# 24Vto5Vat1A-R1.net
KiCad netlist of a schematic drawn in Altium Designer
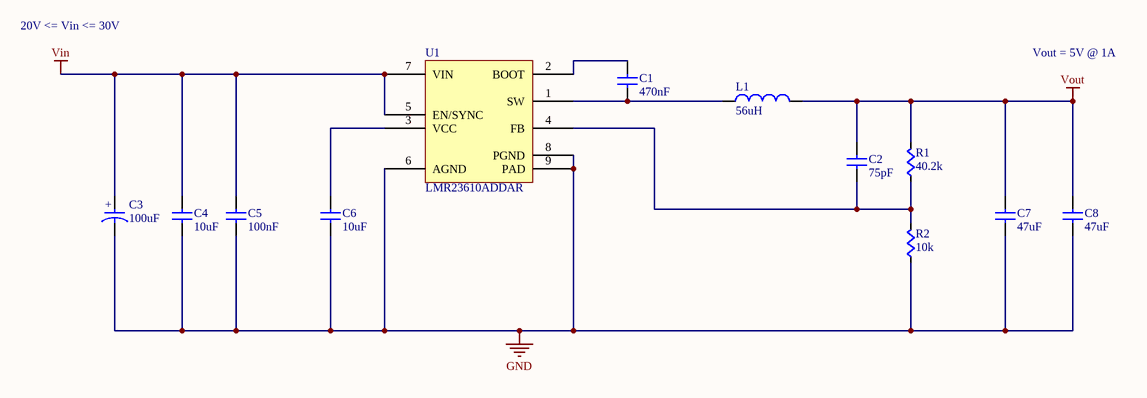
[diagram p0: 24Vto5Vat1A-R1.SchDoc]

(export (version "E")
  (design (tool "Eeschema 10.0.6"))
  (components
    (comp (ref "C1")
      (value "470nF")
      (footprint "CAPC0603")
      (fields (field (name "Comment") "Cap"))
      (libsource (lib "Passives") (part "Cap"))
    )
    (comp (ref "C2")
      (value "75pF")
      (footprint "CAPC0603")
      (fields (field (name "Comment") "Cap"))
      (libsource (lib "Passives") (part "Cap"))
    )
    (comp (ref "C3")
      (value "100uF")
      (footprint "EEHZA1H101P")
      (description "CAP ALUM POLY HYB 100UF 50V SMD")
      (fields (field (name "VOLTAGE") "50V") (field (name "TOLERANCE") "20%"))
      (libsource (lib "SubjuGator8") (part "EEHZA1H101P"))
    )
    (comp (ref "C4")
      (value "10uF")
      (footprint "CAP1210")
      (fields (field (name "Comment") "Cap"))
      (libsource (lib "Passives") (part "Cap"))
    )
    (comp (ref "C5")
      (value "100nF")
      (footprint "CAPC0603")
      (fields (field (name "Comment") "Cap"))
      (libsource (lib "Passives") (part "Cap"))
    )
    (comp (ref "C6")
      (value "10uF")
      (footprint "CAPC0603")
      (fields (field (name "Comment") "Cap"))
      (libsource (lib "Passives") (part "Cap"))
    )
    (comp (ref "C7")
      (value "47uF")
      (footprint "CAP1210")
      (fields (field (name "Comment") "Cap"))
      (libsource (lib "SubjuGator8") (part "Cap"))
    )
    (comp (ref "C8")
      (value "47uF")
      (footprint "CAP1210")
      (fields (field (name "Comment") "Cap"))
      (libsource (lib "SubjuGator8") (part "Cap"))
    )
    (comp (ref "L1")
      (value "56uH")
      (footprint "MSS1048-563MLB")
      (description "FIXED IND 56UH 1.7A 126 MOHM")
      (fields (field (name "Comment") "MSS1048-563MLB"))
      (libsource (lib "SubjuGator8") (part "MSS1048-563MLB"))
    )
    (comp (ref "R1")
      (value "40.2k")
      (footprint "RES0603")
      (fields (field (name "Comment") "Res"))
      (libsource (lib "SubjuGator8") (part "Res"))
    )
    (comp (ref "R2")
      (value "10k")
      (footprint "RES0603")
      (fields (field (name "Comment") "Res"))
      (libsource (lib "SubjuGator8") (part "Res"))
    )
    (comp (ref "U1")
      (value "LMR23610ADDAR")
      (footprint "LMR23610ADDAR")
      (description "IC REG BUCK ADJ 1A SYNC 8SOPWRPD")
      (libsource (lib "SubjuGator8") (part "LMR23610ADDAR"))
    )
  )
  (nets
    (net (code "1") (name "GND") (class "Default")
      (node (ref "C3") (pin "2") (pinfunction "2_2") (pintype "passive"))
      (node (ref "C4") (pin "2") (pinfunction "B_2") (pintype "passive"))
      (node (ref "C5") (pin "2") (pinfunction "B_2") (pintype "passive"))
      (node (ref "C6") (pin "2") (pinfunction "B_2") (pintype "passive"))
      (node (ref "C7") (pin "2") (pinfunction "B_2") (pintype "passive"))
      (node (ref "C8") (pin "2") (pinfunction "B_2") (pintype "passive"))
      (node (ref "R2") (pin "2") (pinfunction "B_2") (pintype "passive"))
      (node (ref "U1") (pin "6") (pinfunction "AGND_6") (pintype "passive"))
      (node (ref "U1") (pin "8") (pinfunction "PGND_8") (pintype "passive"))
      (node (ref "U1") (pin "9") (pinfunction "PAD_9") (pintype "passive"))
    )
    (net (code "2") (name "Net-(C1-A)") (class "Default")
      (node (ref "C1") (pin "1") (pinfunction "A_1") (pintype "passive"))
      (node (ref "U1") (pin "2") (pinfunction "BOOT_2") (pintype "passive"))
    )
    (net (code "3") (name "Net-(C1-B)") (class "Default")
      (node (ref "C1") (pin "2") (pinfunction "B_2") (pintype "passive"))
      (node (ref "L1") (pin "1") (pinfunction "1_1") (pintype "passive"))
      (node (ref "U1") (pin "1") (pinfunction "SW_1") (pintype "passive"))
    )
    (net (code "4") (name "Net-(C2-B)") (class "Default")
      (node (ref "C2") (pin "2") (pinfunction "B_2") (pintype "passive"))
      (node (ref "R1") (pin "2") (pinfunction "B_2") (pintype "passive"))
      (node (ref "R2") (pin "1") (pinfunction "A_1") (pintype "passive"))
      (node (ref "U1") (pin "4") (pinfunction "FB_4") (pintype "passive"))
    )
    (net (code "5") (name "Net-(C6-A)") (class "Default")
      (node (ref "C6") (pin "1") (pinfunction "A_1") (pintype "passive"))
      (node (ref "U1") (pin "3") (pinfunction "VCC_3") (pintype "passive"))
    )
    (net (code "6") (name "Vin") (class "Default")
      (node (ref "C3") (pin "1") (pinfunction "1_1") (pintype "passive"))
      (node (ref "C4") (pin "1") (pinfunction "A_1") (pintype "passive"))
      (node (ref "C5") (pin "1") (pinfunction "A_1") (pintype "passive"))
      (node (ref "U1") (pin "5") (pinfunction "EN/SYNC_5") (pintype "passive"))
      (node (ref "U1") (pin "7") (pinfunction "VIN_7") (pintype "passive"))
    )
    (net (code "7") (name "Vout") (class "Default")
      (node (ref "C2") (pin "1") (pinfunction "A_1") (pintype "passive"))
      (node (ref "C7") (pin "1") (pinfunction "A_1") (pintype "passive"))
      (node (ref "C8") (pin "1") (pinfunction "A_1") (pintype "passive"))
      (node (ref "L1") (pin "2") (pinfunction "2_2") (pintype "passive"))
      (node (ref "R1") (pin "1") (pinfunction "A_1") (pintype "passive"))
    )
  )
)
